# SCH_Hacker-Card_2024-03-24.net
KiCad netlist of a schematic drawn in EasyEDA
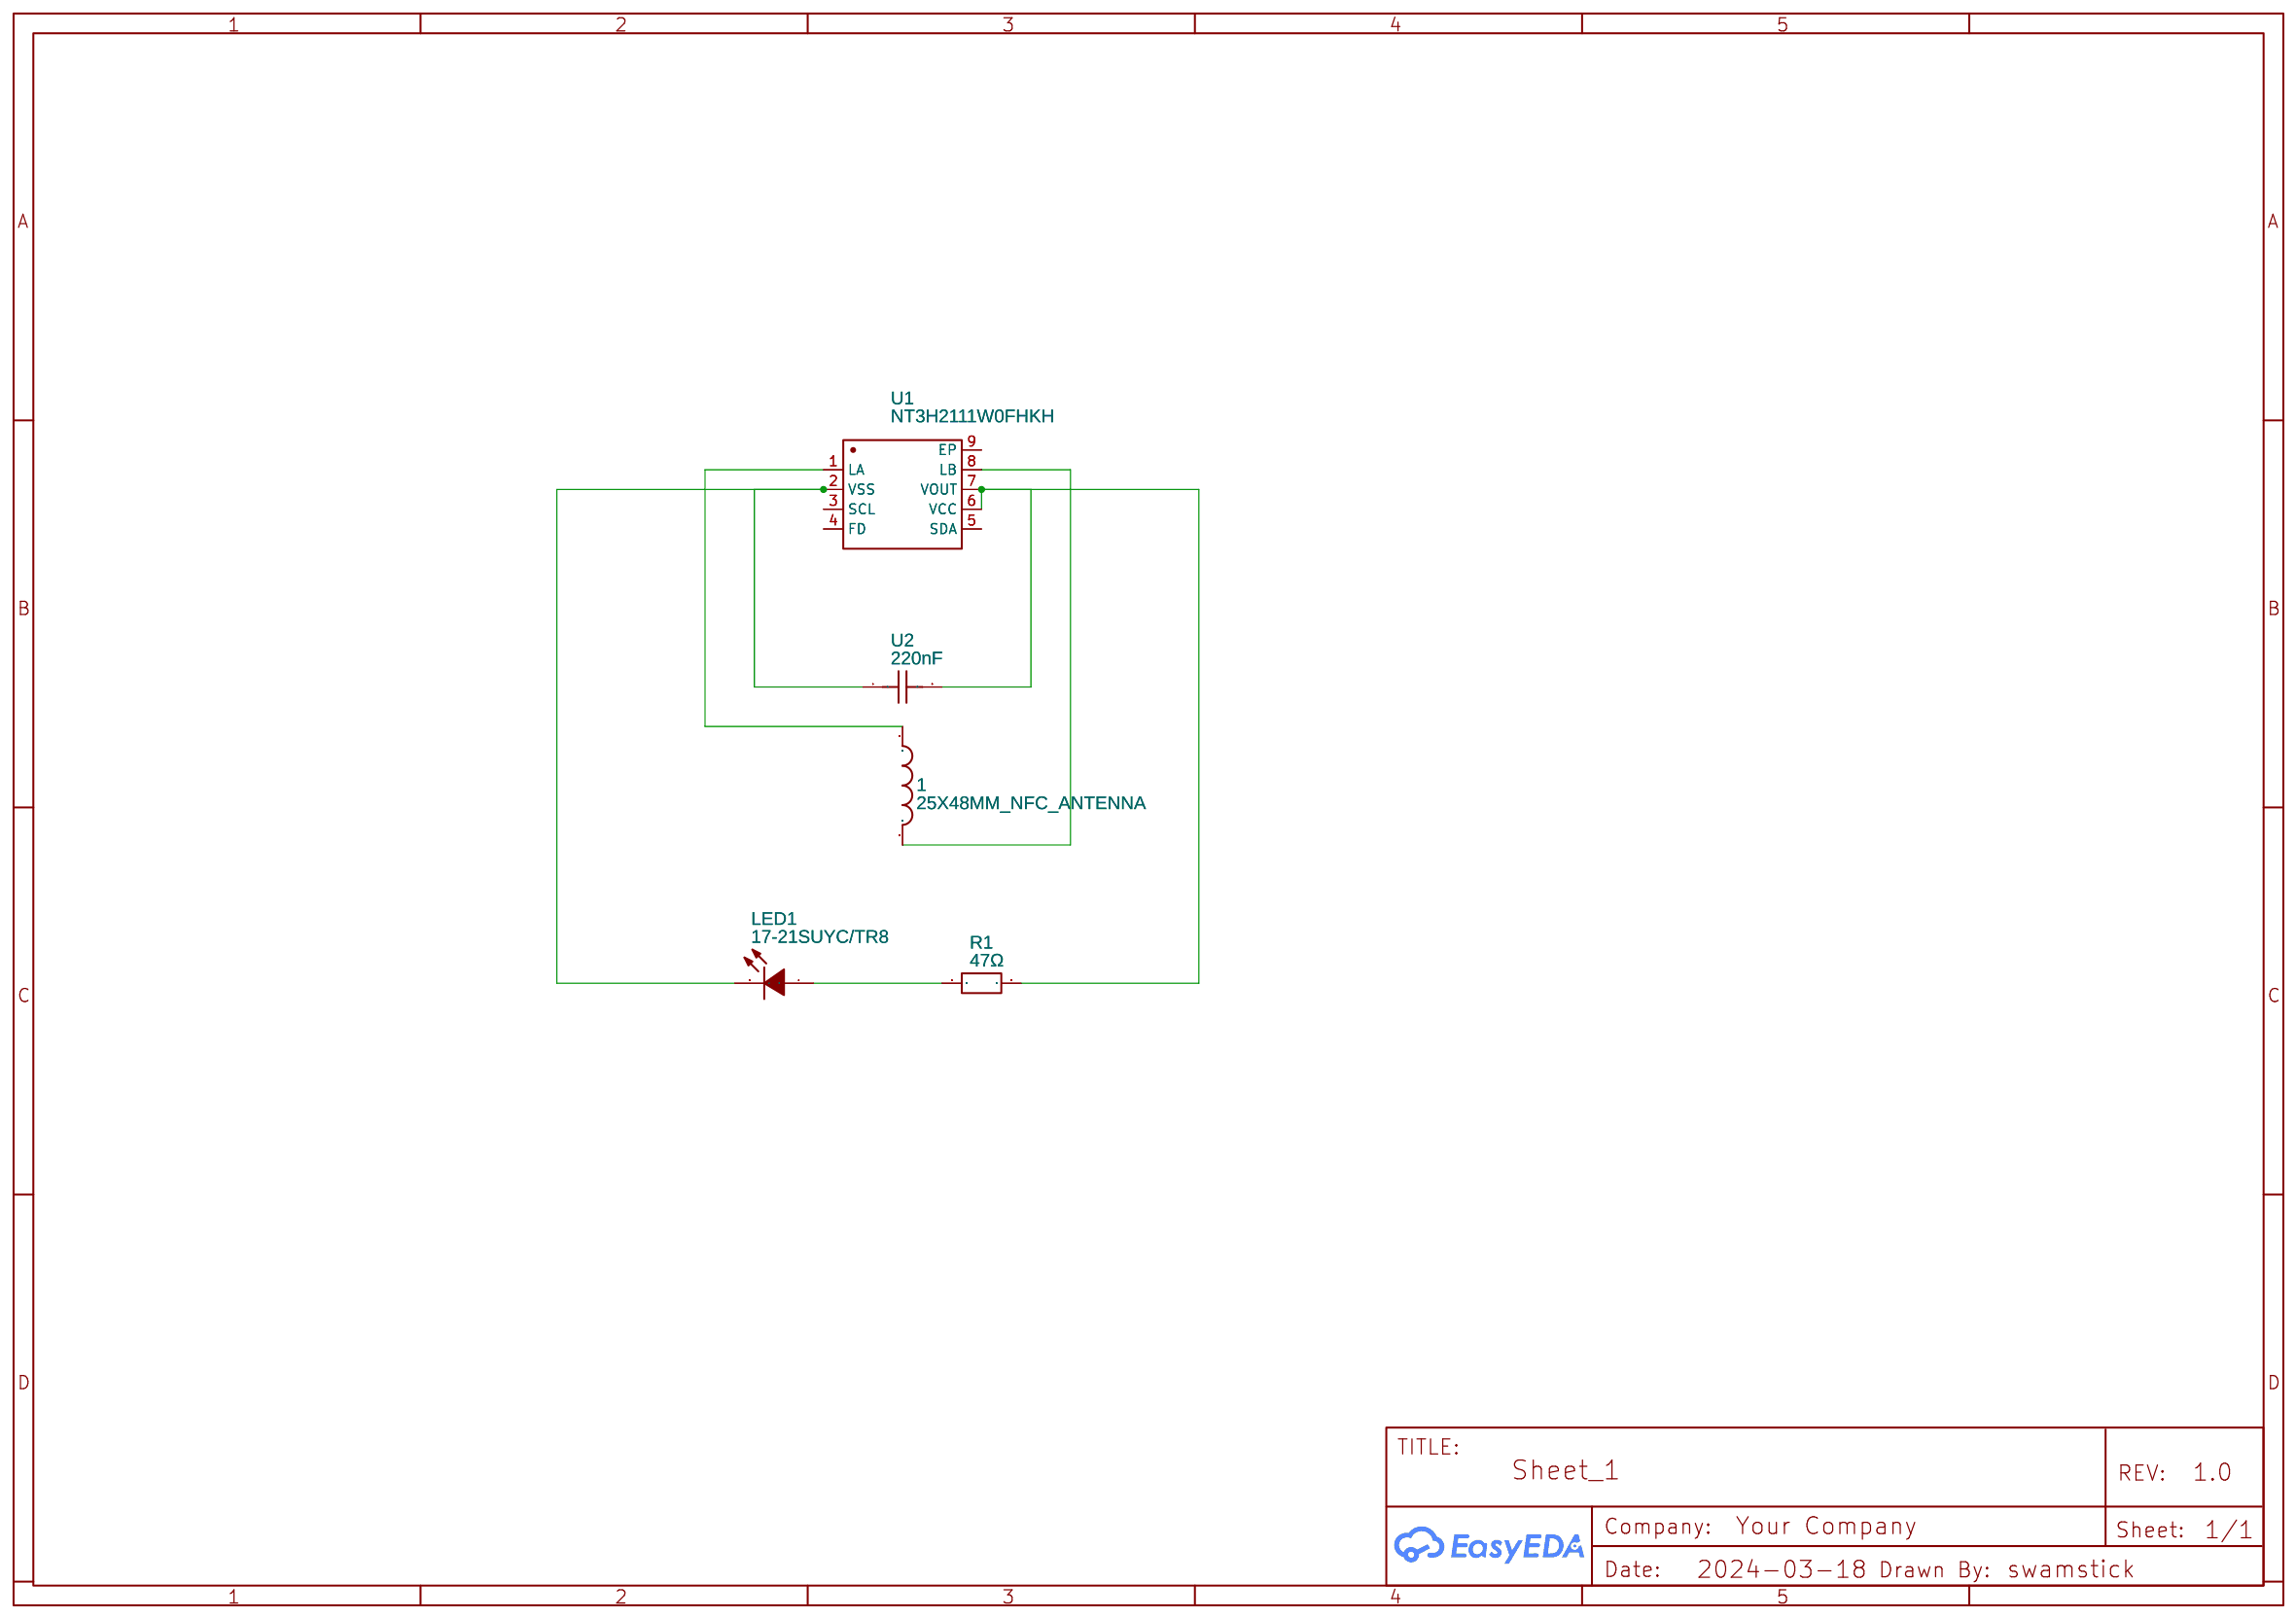
[diagram p0: schematic sheet]

(export (version "E")
  (design (tool "Eeschema 10.0.6"))
  (components
    (comp (ref "1") (value "25X48MM_NFC_ANTENNA") (libsource (lib "") (part "25X48MM_NFC_ANTENNA")))
    (comp (ref "LED1")
      (value "17-21SUYC/TR8")
      (fields (field (name "Manufacturer Part") "KT-0805黄灯") (field (name "Manufacturer") "KENTO"))
      (libsource (lib "") (part "17-21SUYC/TR8"))
    )
    (comp (ref "R1")
      (value "47Ω")
      (fields
        (field (name "Manufacturer Part") "CRCW120647R0FKEA")
        (field (name "Manufacturer") "VISHAY(威世)")
      )
      (libsource (lib "") (part "CRCW120647R0FKEA"))
    )
    (comp (ref "U1")
      (value "NT3H2111W0FHKH")
      (fields (field (name "Manufacturer") "NXP(恩智浦)"))
      (libsource (lib "") (part "NT3H2111W0FHKH"))
    )
    (comp (ref "U2")
      (value "220nF")
      (fields
        (field (name "Manufacturer Part") "UMK105BJ224KV-F")
        (field (name "Manufacturer") "TAIYO YUDEN(太诱)")
      )
      (libsource (lib "") (part "UMK105BJ224KV-F"))
    )
  )
  (nets
    (net (code "1") (name "Net-(LED1-+)") (class "Default")
      (node (ref "LED1") (pin "1") (pinfunction "+_1") (pintype "unspecified"))
      (node (ref "R1") (pin "1") (pinfunction "1_1") (pintype "unspecified"))
    )
    (net (code "2") (name "Net-(LED1--)") (class "Default")
      (node (ref "LED1") (pin "2") (pinfunction "-_2") (pintype "unspecified"))
      (node (ref "U1") (pin "2") (pinfunction "VSS_2") (pintype "unspecified"))
      (node (ref "U2") (pin "1") (pinfunction "1_1") (pintype "unspecified"))
    )
    (net (code "3") (name "Net-(U1-LA)") (class "Default")
      (node (ref "1") (pin "P$1") (pinfunction "P$1_P$1") (pintype "bidirectional"))
      (node (ref "U1") (pin "1") (pinfunction "LA_1") (pintype "unspecified"))
    )
    (net (code "4") (name "Net-(U1-LB)") (class "Default")
      (node (ref "1") (pin "P$2") (pinfunction "P$2_P$2") (pintype "bidirectional"))
      (node (ref "U1") (pin "8") (pinfunction "LB_8") (pintype "unspecified"))
    )
    (net (code "5") (name "Net-(U1-VCC)") (class "Default")
      (node (ref "R1") (pin "2") (pinfunction "2_2") (pintype "unspecified"))
      (node (ref "U1") (pin "6") (pinfunction "VCC_6") (pintype "unspecified"))
      (node (ref "U1") (pin "7") (pinfunction "VOUT_7") (pintype "unspecified"))
      (node (ref "U2") (pin "2") (pinfunction "2_2") (pintype "unspecified"))
    )
    (net (code "6") (name "unconnected-(U1-EP-Pad9)") (class "Default")
      (node (ref "U1") (pin "9") (pinfunction "EP_9") (pintype "unspecified"))
    )
    (net (code "7") (name "unconnected-(U1-FD-Pad4)") (class "Default")
      (node (ref "U1") (pin "4") (pinfunction "FD_4") (pintype "unspecified"))
    )
    (net (code "8") (name "unconnected-(U1-SCL-Pad3)") (class "Default")
      (node (ref "U1") (pin "3") (pinfunction "SCL_3") (pintype "unspecified"))
    )
    (net (code "9") (name "unconnected-(U1-SDA-Pad5)") (class "Default")
      (node (ref "U1") (pin "5") (pinfunction "SDA_5") (pintype "unspecified"))
    )
  )
)
